# tripleir.net
KiCad netlist of a schematic drawn in EAGLE
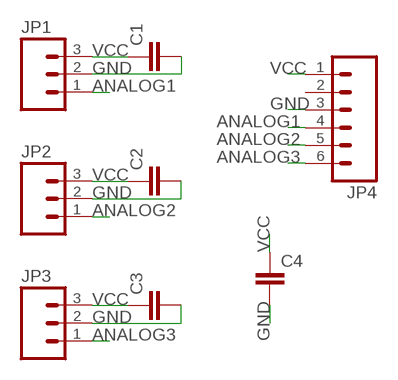
[diagram p0: schematic, sheet 1]

(export (version "E")
  (design (tool "Eeschema 10.0.6"))
  (components
    (comp (ref "C1")
      (value "CAP0603-CAP")
      (footprint "eagle-import:0603-CAP")
      (libsource (lib "eagle-import") (part "CAP0603-CAP"))
    )
    (comp (ref "C2")
      (value "CAP0603-CAP")
      (footprint "eagle-import:0603-CAP")
      (libsource (lib "eagle-import") (part "CAP0603-CAP"))
    )
    (comp (ref "C3")
      (value "CAP0603-CAP")
      (footprint "eagle-import:0603-CAP")
      (libsource (lib "eagle-import") (part "CAP0603-CAP"))
    )
    (comp (ref "C4")
      (value "CAP0603-CAP")
      (footprint "eagle-import:0603-CAP")
      (libsource (lib "eagle-import") (part "CAP0603-CAP"))
    )
    (comp (ref "JP1")
      (value "M03LONGPADS")
      (footprint "eagle-import:1X03_LONGPADS")
      (libsource (lib "eagle-import") (part "M03LONGPADS"))
    )
    (comp (ref "JP2")
      (value "M03LONGPADS")
      (footprint "eagle-import:1X03_LONGPADS")
      (libsource (lib "eagle-import") (part "M03LONGPADS"))
    )
    (comp (ref "JP3")
      (value "M03LONGPADS")
      (footprint "eagle-import:1X03_LONGPADS")
      (libsource (lib "eagle-import") (part "M03LONGPADS"))
    )
    (comp (ref "JP4")
      (value "M06SIP")
      (footprint "eagle-import:1X06")
      (libsource (lib "eagle-import") (part "M06SIP"))
    )
  )
  (nets
    (net (code "1") (name "/ANALOG1") (class "Default")
      (node (ref "JP1") (pin "1") (pinfunction "1_1") (pintype "passive"))
      (node (ref "JP4") (pin "4") (pinfunction "4_4") (pintype "passive"))
    )
    (net (code "2") (name "/ANALOG2") (class "Default")
      (node (ref "JP2") (pin "1") (pinfunction "1_1") (pintype "passive"))
      (node (ref "JP4") (pin "5") (pinfunction "5_5") (pintype "passive"))
    )
    (net (code "3") (name "/ANALOG3") (class "Default")
      (node (ref "JP3") (pin "1") (pinfunction "1_1") (pintype "passive"))
      (node (ref "JP4") (pin "6") (pinfunction "6_6") (pintype "passive"))
    )
    (net (code "4") (name "/GND") (class "Default")
      (node (ref "C1") (pin "2") (pinfunction "2_2") (pintype "passive"))
      (node (ref "C2") (pin "2") (pinfunction "2_2") (pintype "passive"))
      (node (ref "C3") (pin "2") (pinfunction "2_2") (pintype "passive"))
      (node (ref "C4") (pin "2") (pinfunction "2_2") (pintype "passive"))
      (node (ref "JP1") (pin "2") (pinfunction "2_2") (pintype "passive"))
      (node (ref "JP2") (pin "2") (pinfunction "2_2") (pintype "passive"))
      (node (ref "JP3") (pin "2") (pinfunction "2_2") (pintype "passive"))
      (node (ref "JP4") (pin "3") (pinfunction "3_3") (pintype "passive"))
    )
    (net (code "5") (name "/VCC") (class "Default")
      (node (ref "C1") (pin "1") (pinfunction "1_1") (pintype "passive"))
      (node (ref "C2") (pin "1") (pinfunction "1_1") (pintype "passive"))
      (node (ref "C3") (pin "1") (pinfunction "1_1") (pintype "passive"))
      (node (ref "C4") (pin "1") (pinfunction "1_1") (pintype "passive"))
      (node (ref "JP1") (pin "3") (pinfunction "3_3") (pintype "passive"))
      (node (ref "JP2") (pin "3") (pinfunction "3_3") (pintype "passive"))
      (node (ref "JP3") (pin "3") (pinfunction "3_3") (pintype "passive"))
      (node (ref "JP4") (pin "1") (pinfunction "1_1") (pintype "passive"))
    )
    (net (code "6") (name "unconnected-(JP4-Pad2)") (class "Default")
      (node (ref "JP4") (pin "2") (pinfunction "2_2") (pintype "passive"))
    )
  )
)
